# tricorder-teensy-mk-1_9.net
KiCad netlist of a schematic drawn in EAGLE
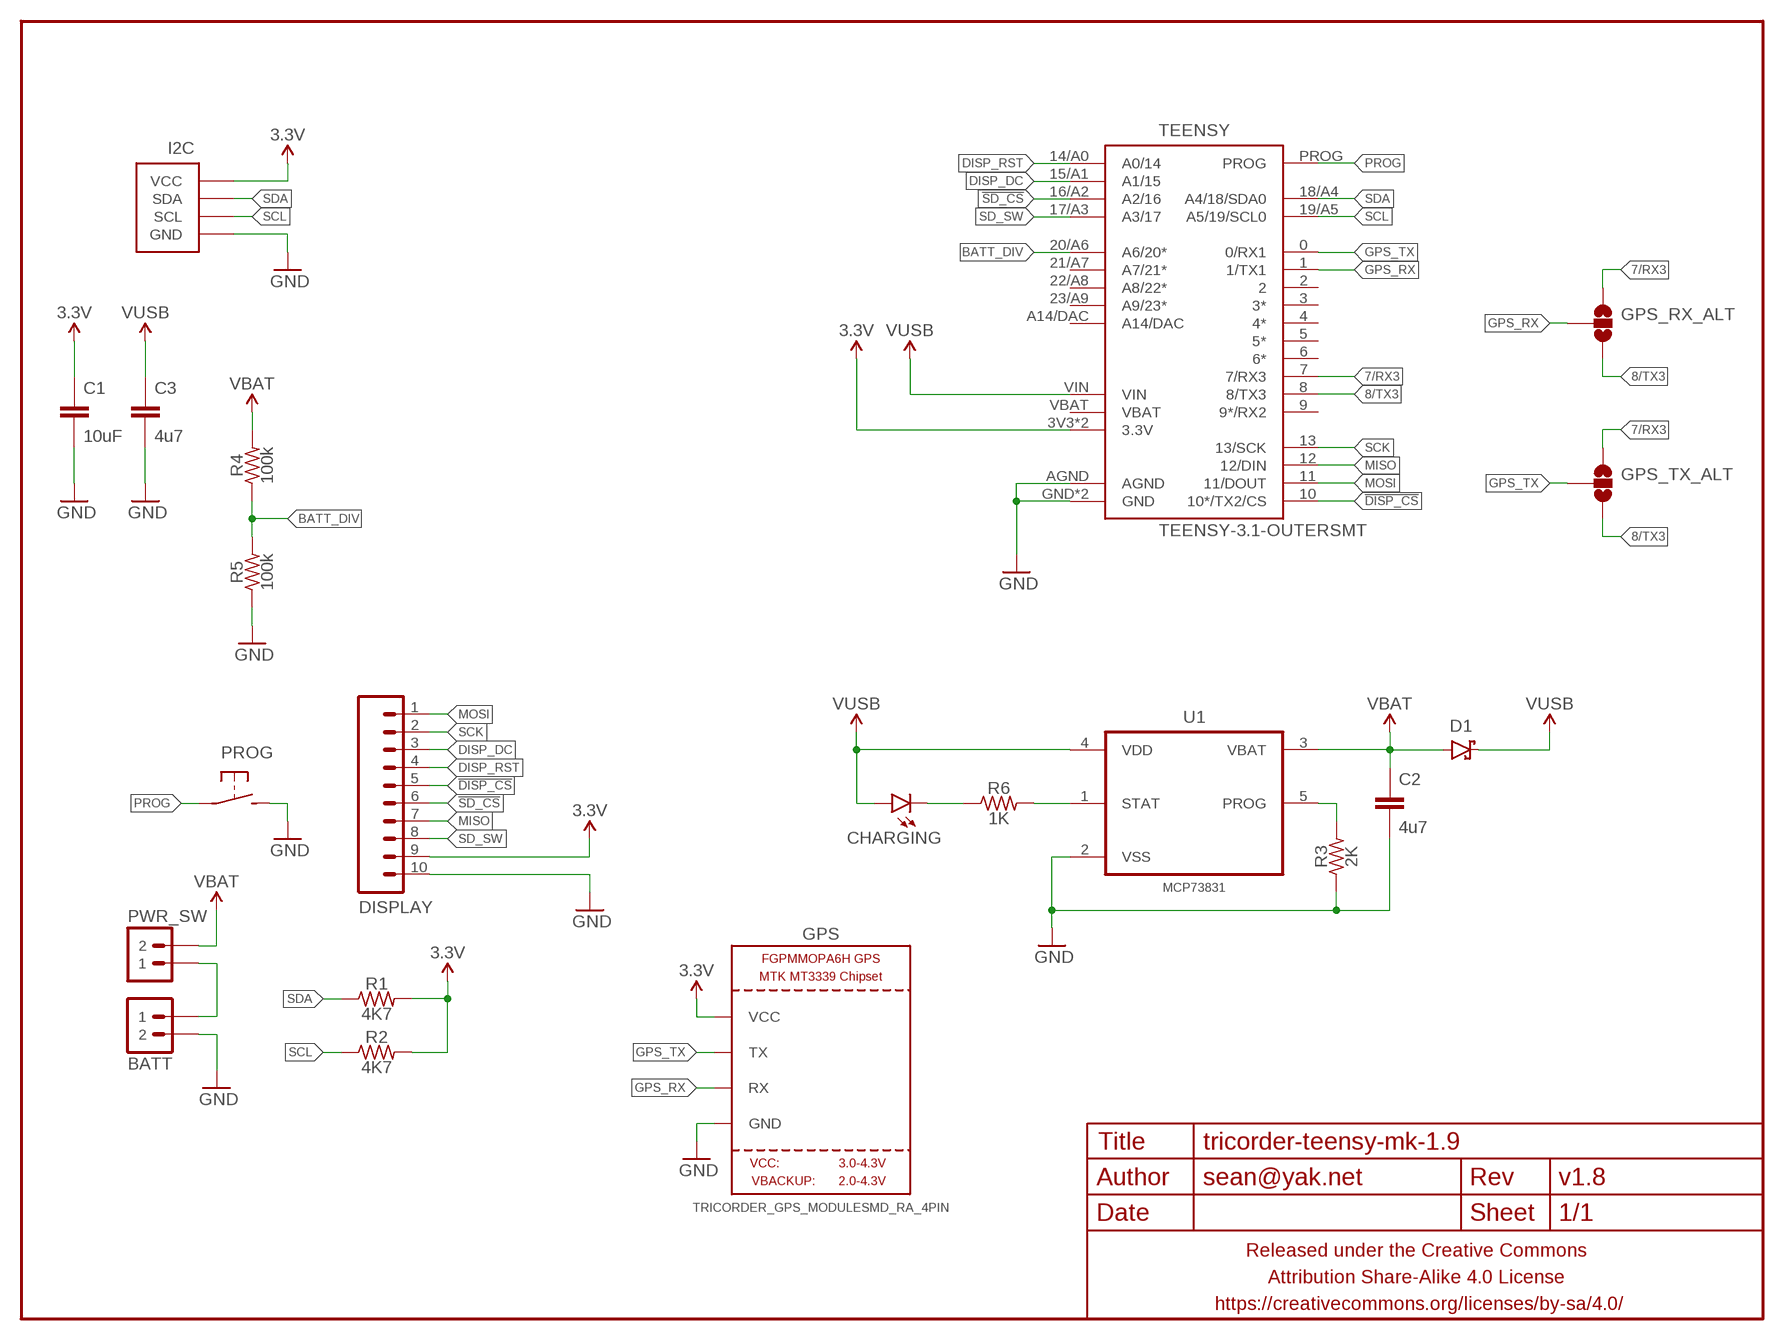
[diagram p0: schematic, sheet 1]

(export (version "E")
  (design (tool "Eeschema 10.0.6"))
  (components
    (comp (ref "BATT")
      (value "M02JST-2MM-SMT")
      (footprint "eagle-import:JST-2-SMD")
      (libsource (lib "eagle-import") (part "M02JST-2MM-SMT"))
    )
    (comp (ref "C1")
      (value "10uF")
      (footprint "eagle-import:C1210")
      (libsource (lib "eagle-import") (part "CAPACITOR-CERAMICC1210"))
    )
    (comp (ref "C2")
      (value "4u7")
      (footprint "eagle-import:C0603-TIGHTER")
      (libsource (lib "eagle-import") (part "CAPACITOR-CERAMICC0603-TIGHTER"))
    )
    (comp (ref "C3")
      (value "4u7")
      (footprint "eagle-import:C0603-TIGHTER")
      (libsource (lib "eagle-import") (part "CAPACITOR-CERAMICC0603-TIGHTER"))
    )
    (comp (ref "CHARGING")
      (value "LED0603-TIGHT")
      (footprint "eagle-import:LED-0603-TIGHT")
      (libsource (lib "eagle-import") (part "LED0603-TIGHT"))
    )
    (comp (ref "D1")
      (value "DIODE-SCHOTTKYSOD123")
      (footprint "eagle-import:SOD123-SCHOTTKY")
      (libsource (lib "eagle-import") (part "DIODE-SCHOTTKYSOD123"))
    )
    (comp (ref "DISPLAY")
      (value "M10SMD_RA_2MM")
      (footprint "eagle-import:1X10_SMD_RA_MALE")
      (libsource (lib "eagle-import") (part "M10SMD_RA_2MM"))
    )
    (comp (ref "FRAME1")
      (value "FRAME-LETTERNO_PACKAGE")
      (footprint "eagle-import:DUMMY")
      (fields (field (name "DESIGNER") "sean@yak.net") (field (name "VERSION") "v1.8"))
      (libsource (lib "eagle-import") (part "FRAME-LETTERNO_PACKAGE"))
    )
    (comp (ref "GPS")
      (value "TRICORDER_GPS_MODULESMD_RA_4PIN")
      (footprint "eagle-import:TRICORDER_GPS_MODULE_RA_CONN_SMD_4PIN")
      (libsource (lib "eagle-import") (part "TRICORDER_GPS_MODULESMD_RA_4PIN"))
    )
    (comp (ref "GPS_RX_ALT")
      (value "JUMPER-PAD-3-NOFULL_BOX_SILK")
      (footprint "eagle-import:PAD-JUMPER-3-NO_YES_SILK_FULL_BOX")
      (libsource (lib "eagle-import") (part "JUMPER-PAD-3-NOFULL_BOX_SILK"))
    )
    (comp (ref "GPS_TX_ALT")
      (value "JUMPER-PAD-3-NOFULL_BOX_SILK")
      (footprint "eagle-import:PAD-JUMPER-3-NO_YES_SILK_FULL_BOX")
      (libsource (lib "eagle-import") (part "JUMPER-PAD-3-NOFULL_BOX_SILK"))
    )
    (comp (ref "I2C")
      (value "M04-I2CSMD_2MM_RA")
      (footprint "eagle-import:1X04_SMD_RA_2MM_I2C")
      (libsource (lib "eagle-import") (part "M04-I2CSMD_2MM_RA"))
    )
    (comp (ref "PROG")
      (value "SPST-NO-TACTCK-PTS840-GK")
      (footprint "eagle-import:TACTILE-SMD-CK-PTS840-GK")
      (libsource (lib "eagle-import") (part "SPST-NO-TACTCK-PTS840-GK"))
    )
    (comp (ref "PWR_SW")
      (value "M02JST-2MM-SMT")
      (footprint "eagle-import:JST-2-SMD")
      (libsource (lib "eagle-import") (part "M02JST-2MM-SMT"))
    )
    (comp (ref "R1")
      (value "4K7")
      (footprint "eagle-import:R0603-TIGHTER")
      (libsource (lib "eagle-import") (part "RESISTORR0603-TIGHTER"))
    )
    (comp (ref "R2")
      (value "4K7")
      (footprint "eagle-import:R0603-TIGHTER")
      (libsource (lib "eagle-import") (part "RESISTORR0603-TIGHTER"))
    )
    (comp (ref "R3")
      (value "2K")
      (footprint "eagle-import:R0603-TIGHTER")
      (libsource (lib "eagle-import") (part "RESISTORR0603-TIGHTER"))
    )
    (comp (ref "R4")
      (value "100k")
      (footprint "eagle-import:R0603-TIGHTER")
      (libsource (lib "eagle-import") (part "RESISTORR0603-TIGHTER"))
    )
    (comp (ref "R5")
      (value "100k")
      (footprint "eagle-import:R0603-TIGHTER")
      (libsource (lib "eagle-import") (part "RESISTORR0603-TIGHTER"))
    )
    (comp (ref "R6")
      (value "1K")
      (footprint "eagle-import:R0603-TIGHTER")
      (libsource (lib "eagle-import") (part "RESISTORR0603-TIGHTER"))
    )
    (comp (ref "TEENSY")
      (value "TEENSY-3.1-OUTERSMT")
      (footprint "eagle-import:TEENSY-3.1_SMT_BOTTOM_OUTERONLY")
      (libsource (lib "eagle-import") (part "TEENSY-3.1-OUTERSMT"))
    )
    (comp (ref "U1")
      (value "MCP73831")
      (footprint "eagle-import:SOT95P280X145-5N")
      (fields (field (name "MPN") "MCP73831T-2ACI/OT"))
      (libsource (lib "eagle-import") (part "MCP73831T-2ACI/OT"))
    )
  )
  (nets
    (net (code "1") (name "/~{DISP_CS}") (class "Default")
      (node (ref "DISPLAY") (pin "5") (pinfunction "5_5") (pintype "passive"))
      (node (ref "TEENSY") (pin "10") (pinfunction "10*/TX2/CS_10") (pintype "bidirectional"))
    )
    (net (code "2") (name "/~{SD_CS}") (class "Default")
      (node (ref "DISPLAY") (pin "6") (pinfunction "6_6") (pintype "passive"))
      (node (ref "TEENSY") (pin "16/A2") (pinfunction "A2/16_16/A2") (pintype "bidirectional"))
    )
    (net (code "3") (name "3.3V") (class "Default")
      (node (ref "C1") (pin "1") (pinfunction "1_1") (pintype "passive"))
      (node (ref "DISPLAY") (pin "9") (pinfunction "9_9") (pintype "passive"))
      (node (ref "GPS") (pin "VCC") (pinfunction "VCC_VCC") (pintype "bidirectional"))
      (node (ref "I2C") (pin "VCC") (pinfunction "VCC_VCC") (pintype "bidirectional"))
      (node (ref "R1") (pin "2") (pinfunction "2_2") (pintype "passive"))
      (node (ref "R2") (pin "2") (pinfunction "2_2") (pintype "passive"))
      (node (ref "TEENSY") (pin "3V3") (pinfunction "3.3V_3V3") (pintype "bidirectional"))
      (node (ref "TEENSY") (pin "3V3@1") (pinfunction "3.3V_3V3@1") (pintype "bidirectional"))
    )
    (net (code "4") (name "7{slash}RX3") (class "Default")
      (node (ref "GPS_RX_ALT") (pin "1") (pinfunction "1_1") (pintype "passive"))
      (node (ref "GPS_TX_ALT") (pin "1") (pinfunction "1_1") (pintype "passive"))
      (node (ref "TEENSY") (pin "7") (pinfunction "7/RX3_7") (pintype "bidirectional"))
    )
    (net (code "5") (name "8{slash}TX3") (class "Default")
      (node (ref "GPS_RX_ALT") (pin "3") (pinfunction "3_3") (pintype "passive"))
      (node (ref "GPS_TX_ALT") (pin "3") (pinfunction "3_3") (pintype "passive"))
      (node (ref "TEENSY") (pin "8") (pinfunction "8/TX3_8") (pintype "bidirectional"))
    )
    (net (code "6") (name "BATT_DIV") (class "Default")
      (node (ref "R4") (pin "1") (pinfunction "1_1") (pintype "passive"))
      (node (ref "R5") (pin "2") (pinfunction "2_2") (pintype "passive"))
      (node (ref "TEENSY") (pin "20/A6") (pinfunction "A6/20*_20/A6") (pintype "bidirectional"))
    )
    (net (code "7") (name "DISP_DC") (class "Default")
      (node (ref "DISPLAY") (pin "3") (pinfunction "3_3") (pintype "passive"))
      (node (ref "TEENSY") (pin "15/A1") (pinfunction "A1/15_15/A1") (pintype "bidirectional"))
    )
    (net (code "8") (name "DISP_RST") (class "Default")
      (node (ref "DISPLAY") (pin "4") (pinfunction "4_4") (pintype "passive"))
      (node (ref "TEENSY") (pin "14/A0") (pinfunction "A0/14_14/A0") (pintype "bidirectional"))
    )
    (net (code "9") (name "GND") (class "Default")
      (node (ref "BATT") (pin "1") (pinfunction "2_1") (pintype "passive"))
      (node (ref "C1") (pin "2") (pinfunction "2_2") (pintype "passive"))
      (node (ref "C2") (pin "2") (pinfunction "2_2") (pintype "passive"))
      (node (ref "C3") (pin "2") (pinfunction "2_2") (pintype "passive"))
      (node (ref "DISPLAY") (pin "10") (pinfunction "10_10") (pintype "passive"))
      (node (ref "GPS") (pin "GND") (pinfunction "GND_GND") (pintype "bidirectional"))
      (node (ref "I2C") (pin "GND") (pinfunction "GND_GND") (pintype "bidirectional"))
      (node (ref "PROG") (pin "3") (pinfunction "2_3") (pintype "passive"))
      (node (ref "PROG") (pin "4") (pinfunction "2_4") (pintype "passive"))
      (node (ref "R3") (pin "1") (pinfunction "1_1") (pintype "passive"))
      (node (ref "R5") (pin "1") (pinfunction "1_1") (pintype "passive"))
      (node (ref "TEENSY") (pin "AGND") (pinfunction "AGND_AGND") (pintype "bidirectional"))
      (node (ref "TEENSY") (pin "GND") (pinfunction "GND_GND") (pintype "bidirectional"))
      (node (ref "TEENSY") (pin "GND@1") (pinfunction "GND_GND@1") (pintype "bidirectional"))
      (node (ref "U1") (pin "2") (pinfunction "VSS_2") (pintype "power_in"))
    )
    (net (code "10") (name "GPS_RX") (class "Default")
      (node (ref "GPS") (pin "RX") (pinfunction "RX_RX") (pintype "bidirectional"))
      (node (ref "GPS_RX_ALT") (pin "2") (pinfunction "2_2") (pintype "passive"))
      (node (ref "TEENSY") (pin "1") (pinfunction "1/TX1_1") (pintype "bidirectional"))
    )
    (net (code "11") (name "GPS_TX") (class "Default")
      (node (ref "GPS") (pin "TX") (pinfunction "TX_TX") (pintype "bidirectional"))
      (node (ref "GPS_TX_ALT") (pin "2") (pinfunction "2_2") (pintype "passive"))
      (node (ref "TEENSY") (pin "0") (pinfunction "0/RX1_0") (pintype "bidirectional"))
    )
    (net (code "12") (name "MISO") (class "Default")
      (node (ref "DISPLAY") (pin "7") (pinfunction "7_7") (pintype "passive"))
      (node (ref "TEENSY") (pin "12") (pinfunction "12/DIN_12") (pintype "bidirectional"))
    )
    (net (code "13") (name "MOSI") (class "Default")
      (node (ref "DISPLAY") (pin "1") (pinfunction "1_1") (pintype "passive"))
      (node (ref "TEENSY") (pin "11") (pinfunction "11/DOUT_11") (pintype "bidirectional"))
    )
    (net (code "14") (name "Net-(BATT-1)") (class "Default")
      (node (ref "BATT") (pin "2") (pinfunction "1_2") (pintype "passive"))
      (node (ref "PWR_SW") (pin "2") (pinfunction "1_2") (pintype "passive"))
    )
    (net (code "15") (name "Net-(CHARGING-PadC)") (class "Default")
      (node (ref "CHARGING") (pin "C") (pinfunction "C_C") (pintype "passive"))
      (node (ref "R6") (pin "1") (pinfunction "1_1") (pintype "passive"))
    )
    (net (code "16") (name "Net-(U1-PROG)") (class "Default")
      (node (ref "R3") (pin "2") (pinfunction "2_2") (pintype "passive"))
      (node (ref "U1") (pin "5") (pinfunction "PROG_5") (pintype "input"))
    )
    (net (code "17") (name "Net-(U1-STAT)") (class "Default")
      (node (ref "R6") (pin "2") (pinfunction "2_2") (pintype "passive"))
      (node (ref "U1") (pin "1") (pinfunction "STAT_1") (pintype "output"))
    )
    (net (code "18") (name "PROG") (class "Default")
      (node (ref "PROG") (pin "1") (pinfunction "1_1") (pintype "passive"))
      (node (ref "PROG") (pin "2") (pinfunction "1_2") (pintype "passive"))
      (node (ref "TEENSY") (pin "PROG") (pinfunction "PROG_PROG") (pintype "bidirectional"))
    )
    (net (code "19") (name "SCK") (class "Default")
      (node (ref "DISPLAY") (pin "2") (pinfunction "2_2") (pintype "passive"))
      (node (ref "TEENSY") (pin "13") (pinfunction "13/SCK_13") (pintype "bidirectional"))
    )
    (net (code "20") (name "SCL") (class "Default")
      (node (ref "I2C") (pin "SCL") (pinfunction "SCL_SCL") (pintype "bidirectional"))
      (node (ref "R2") (pin "1") (pinfunction "1_1") (pintype "passive"))
      (node (ref "TEENSY") (pin "19/A5") (pinfunction "A5/19/SCL0_19/A5") (pintype "bidirectional"))
    )
    (net (code "21") (name "SDA") (class "Default")
      (node (ref "I2C") (pin "SDA") (pinfunction "SDA_SDA") (pintype "bidirectional"))
      (node (ref "R1") (pin "1") (pinfunction "1_1") (pintype "passive"))
      (node (ref "TEENSY") (pin "18/A4") (pinfunction "A4/18/SDA0_18/A4") (pintype "bidirectional"))
    )
    (net (code "22") (name "SD_SW") (class "Default")
      (node (ref "DISPLAY") (pin "8") (pinfunction "8_8") (pintype "passive"))
      (node (ref "TEENSY") (pin "17/A3") (pinfunction "A3/17_17/A3") (pintype "bidirectional"))
    )
    (net (code "23") (name "VBAT") (class "Default")
      (node (ref "C2") (pin "1") (pinfunction "1_1") (pintype "passive"))
      (node (ref "D1") (pin "A") (pinfunction "A_A") (pintype "passive"))
      (node (ref "PWR_SW") (pin "1") (pinfunction "2_1") (pintype "passive"))
      (node (ref "R4") (pin "2") (pinfunction "2_2") (pintype "passive"))
      (node (ref "U1") (pin "3") (pinfunction "VBAT_3") (pintype "output"))
    )
    (net (code "24") (name "VUSB") (class "Default")
      (node (ref "C3") (pin "1") (pinfunction "1_1") (pintype "passive"))
      (node (ref "CHARGING") (pin "A") (pinfunction "A_A") (pintype "passive"))
      (node (ref "D1") (pin "C") (pinfunction "C_C") (pintype "passive"))
      (node (ref "TEENSY") (pin "VIN") (pinfunction "VIN_VIN") (pintype "bidirectional"))
      (node (ref "U1") (pin "4") (pinfunction "VDD_4") (pintype "power_in"))
    )
    (net (code "25") (name "unconnected-(TEENSY-3*-Pad3)") (class "Default")
      (node (ref "TEENSY") (pin "3") (pinfunction "3*_3") (pintype "bidirectional"))
    )
    (net (code "26") (name "unconnected-(TEENSY-4*-Pad4)") (class "Default")
      (node (ref "TEENSY") (pin "4") (pinfunction "4*_4") (pintype "bidirectional"))
    )
    (net (code "27") (name "unconnected-(TEENSY-5*-Pad5)") (class "Default")
      (node (ref "TEENSY") (pin "5") (pinfunction "5*_5") (pintype "bidirectional"))
    )
    (net (code "28") (name "unconnected-(TEENSY-6*-Pad6)") (class "Default")
      (node (ref "TEENSY") (pin "6") (pinfunction "6*_6") (pintype "bidirectional"))
    )
    (net (code "29") (name "unconnected-(TEENSY-9*{slash}RX2-Pad9)") (class "Default")
      (node (ref "TEENSY") (pin "9") (pinfunction "9*/RX2_9") (pintype "bidirectional"))
    )
    (net (code "30") (name "unconnected-(TEENSY-A7{slash}21*-Pad21{slash}A7)") (class "Default")
      (node (ref "TEENSY") (pin "21/A7") (pinfunction "A7/21*_21/A7") (pintype "bidirectional"))
    )
    (net (code "31") (name "unconnected-(TEENSY-A8{slash}22*-Pad22{slash}A8)") (class "Default")
      (node (ref "TEENSY") (pin "22/A8") (pinfunction "A8/22*_22/A8") (pintype "bidirectional"))
    )
    (net (code "32") (name "unconnected-(TEENSY-A9{slash}23*-Pad23{slash}A9)") (class "Default")
      (node (ref "TEENSY") (pin "23/A9") (pinfunction "A9/23*_23/A9") (pintype "bidirectional"))
    )
    (net (code "33") (name "unconnected-(TEENSY-Pad2)") (class "Default")
      (node (ref "TEENSY") (pin "2") (pinfunction "2_2") (pintype "bidirectional"))
    )
    (net (code "34") (name "unconnected-(TEENSY-PadA14{slash}DAC)") (class "Default")
      (node (ref "TEENSY") (pin "A14/DAC") (pinfunction "A14/DAC_A14/DAC") (pintype "bidirectional"))
    )
    (net (code "35") (name "unconnected-(TEENSY-PadVBAT)") (class "Default")
      (node (ref "TEENSY") (pin "VBAT") (pinfunction "VBAT_VBAT") (pintype "bidirectional"))
    )
  )
)
